# aw_801_oscilloscope.net
KiCad netlist of a schematic drawn in EAGLE
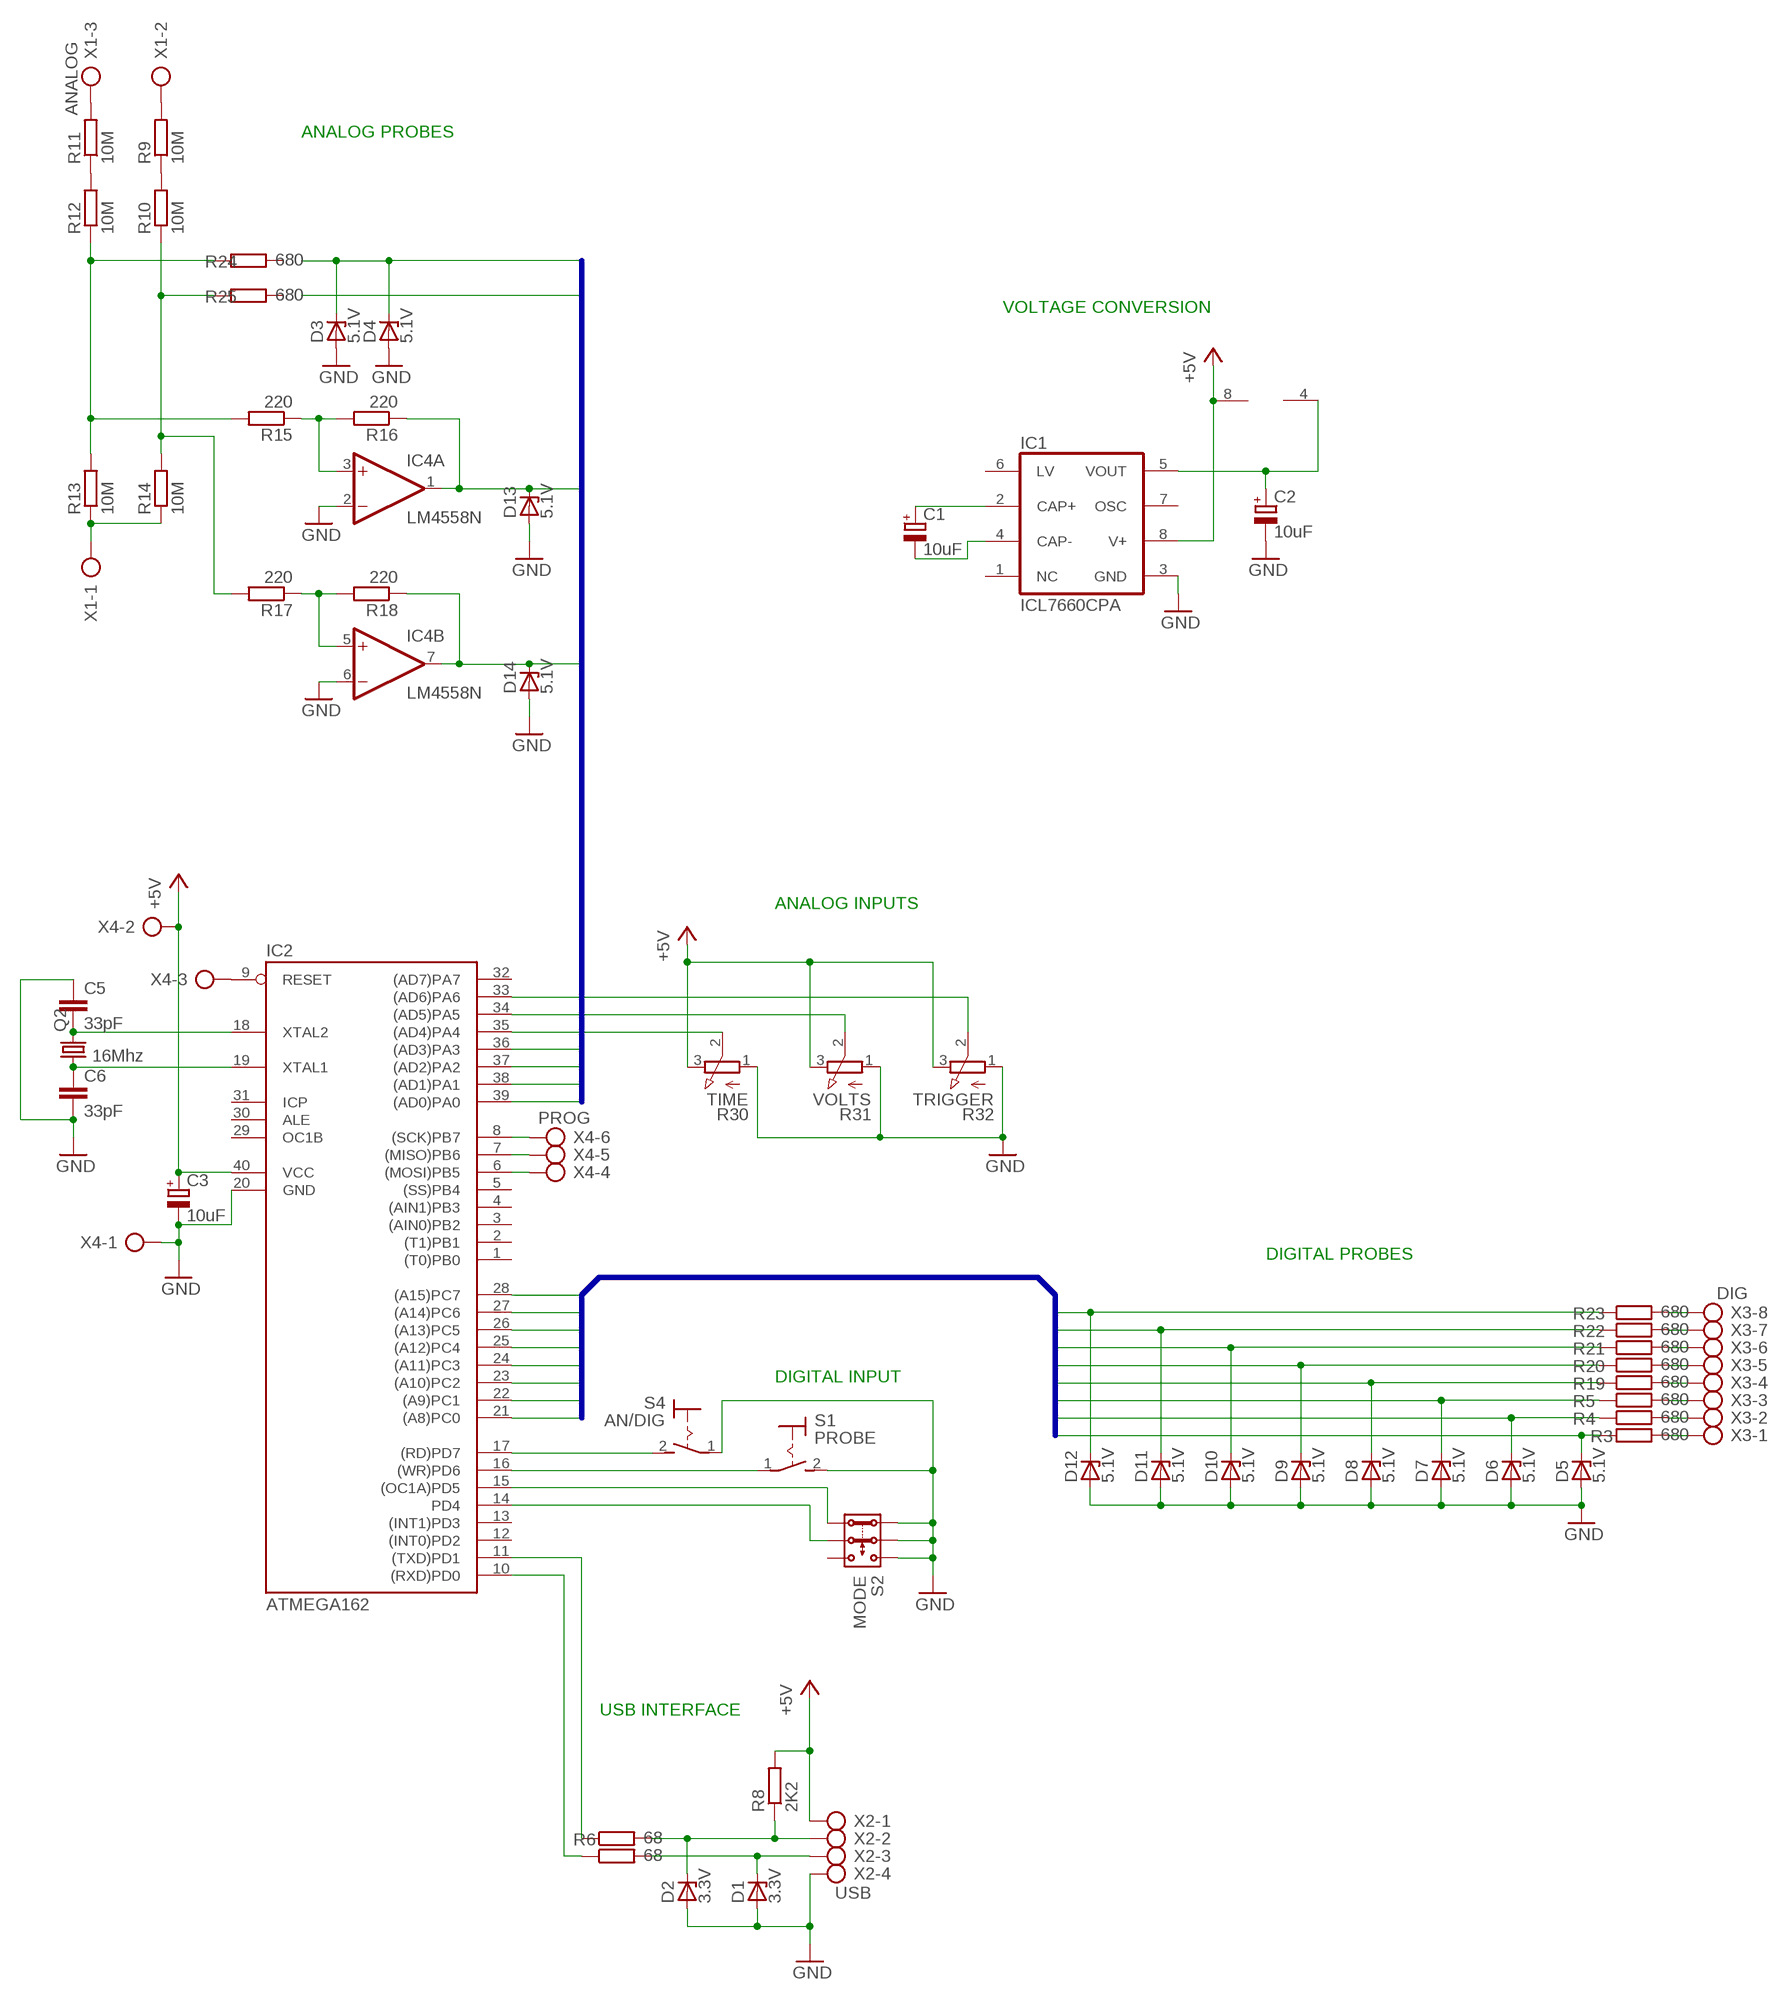
[diagram p0: schematic, sheet 1]

(export (version "E")
  (design (tool "Eeschema 10.0.6"))
  (components
    (comp (ref "C1")
      (value "10uF")
      (footprint "eagle-import:E2,5-6")
      (libsource (lib "eagle-import") (part "CPOL-EUE2.5-6"))
    )
    (comp (ref "C2")
      (value "10uF")
      (footprint "eagle-import:E2,5-6")
      (libsource (lib "eagle-import") (part "CPOL-EUE2.5-6"))
    )
    (comp (ref "C3")
      (value "10uF")
      (footprint "eagle-import:E2,5-6")
      (libsource (lib "eagle-import") (part "CPOL-EUE2.5-6"))
    )
    (comp (ref "C5")
      (value "33pF")
      (footprint "eagle-import:C050-030X075")
      (libsource (lib "eagle-import") (part "C-EU050-030X075"))
    )
    (comp (ref "C6")
      (value "33pF")
      (footprint "eagle-import:C050-030X075")
      (libsource (lib "eagle-import") (part "C-EU050-030X075"))
    )
    (comp (ref "D1")
      (value "3.3V")
      (footprint "eagle-import:DO35Z10")
      (libsource (lib "eagle-import") (part "ZENER-DIODEDO35Z10"))
    )
    (comp (ref "D2")
      (value "3.3V")
      (footprint "eagle-import:DO35Z10")
      (libsource (lib "eagle-import") (part "ZENER-DIODEDO35Z10"))
    )
    (comp (ref "D3")
      (value "5.1V")
      (footprint "eagle-import:DO35Z10")
      (libsource (lib "eagle-import") (part "ZENER-DIODEDO35Z10"))
    )
    (comp (ref "D4")
      (value "5.1V")
      (footprint "eagle-import:DO35Z10")
      (libsource (lib "eagle-import") (part "ZENER-DIODEDO35Z10"))
    )
    (comp (ref "D5")
      (value "5.1V")
      (footprint "eagle-import:DO35Z10")
      (libsource (lib "eagle-import") (part "ZENER-DIODEDO35Z10"))
    )
    (comp (ref "D6")
      (value "5.1V")
      (footprint "eagle-import:DO35Z10")
      (libsource (lib "eagle-import") (part "ZENER-DIODEDO35Z10"))
    )
    (comp (ref "D7")
      (value "5.1V")
      (footprint "eagle-import:DO35Z10")
      (libsource (lib "eagle-import") (part "ZENER-DIODEDO35Z10"))
    )
    (comp (ref "D8")
      (value "5.1V")
      (footprint "eagle-import:DO35Z10")
      (libsource (lib "eagle-import") (part "ZENER-DIODEDO35Z10"))
    )
    (comp (ref "D9")
      (value "5.1V")
      (footprint "eagle-import:DO35Z10")
      (libsource (lib "eagle-import") (part "ZENER-DIODEDO35Z10"))
    )
    (comp (ref "D10")
      (value "5.1V")
      (footprint "eagle-import:DO35Z10")
      (libsource (lib "eagle-import") (part "ZENER-DIODEDO35Z10"))
    )
    (comp (ref "D11")
      (value "5.1V")
      (footprint "eagle-import:DO35Z10")
      (libsource (lib "eagle-import") (part "ZENER-DIODEDO35Z10"))
    )
    (comp (ref "D12")
      (value "5.1V")
      (footprint "eagle-import:DO35Z10")
      (libsource (lib "eagle-import") (part "ZENER-DIODEDO35Z10"))
    )
    (comp (ref "D13")
      (value "5.1V")
      (footprint "eagle-import:DO35Z10")
      (libsource (lib "eagle-import") (part "ZENER-DIODEDO35Z10"))
    )
    (comp (ref "D14")
      (value "5.1V")
      (footprint "eagle-import:DO35Z10")
      (libsource (lib "eagle-import") (part "ZENER-DIODEDO35Z10"))
    )
    (comp (ref "IC1")
      (value "ICL7660CPA")
      (footprint "eagle-import:DIL08")
      (fields (field (name "MF") "INTERSIL"))
      (libsource (lib "eagle-import") (part "ICL7660CPA"))
    )
    (comp (ref "IC2")
      (value "ATMEGA162")
      (footprint "eagle-import:DIL40")
      (libsource (lib "eagle-import") (part "AT90S8515P"))
    )
    (comp (ref "IC4")
      (value "LM4558N")
      (footprint "eagle-import:DIL08")
      (libsource (lib "eagle-import") (part "4558NLM"))
    )
    (comp (ref "Q2")
      (value "16Mhz")
      (footprint "eagle-import:HC49U70")
      (libsource (lib "eagle-import") (part "CRYSTALHC49U70"))
    )
    (comp (ref "R3")
      (value "680")
      (footprint "eagle-import:0207_10")
      (libsource (lib "eagle-import") (part "R-EU_0207/10"))
    )
    (comp (ref "R4")
      (value "680")
      (footprint "eagle-import:0207_10")
      (libsource (lib "eagle-import") (part "R-EU_0207/10"))
    )
    (comp (ref "R5")
      (value "680")
      (footprint "eagle-import:0207_10")
      (libsource (lib "eagle-import") (part "R-EU_0207/10"))
    )
    (comp (ref "R6")
      (value "68")
      (footprint "eagle-import:0207_10")
      (libsource (lib "eagle-import") (part "R-EU_0207/10"))
    )
    (comp (ref "R7")
      (value "68")
      (footprint "eagle-import:0207_10")
      (libsource (lib "eagle-import") (part "R-EU_0207/10"))
    )
    (comp (ref "R8")
      (value "2K2")
      (footprint "eagle-import:0207_10")
      (libsource (lib "eagle-import") (part "R-EU_0207/10"))
    )
    (comp (ref "R9")
      (value "10M")
      (footprint "eagle-import:0207_10")
      (libsource (lib "eagle-import") (part "R-EU_0207/10"))
    )
    (comp (ref "R10")
      (value "10M")
      (footprint "eagle-import:0207_10")
      (libsource (lib "eagle-import") (part "R-EU_0207/10"))
    )
    (comp (ref "R11")
      (value "10M")
      (footprint "eagle-import:0207_10")
      (libsource (lib "eagle-import") (part "R-EU_0207/10"))
    )
    (comp (ref "R12")
      (value "10M")
      (footprint "eagle-import:0207_10")
      (libsource (lib "eagle-import") (part "R-EU_0207/10"))
    )
    (comp (ref "R13")
      (value "10M")
      (footprint "eagle-import:0207_10")
      (libsource (lib "eagle-import") (part "R-EU_0207/10"))
    )
    (comp (ref "R14")
      (value "10M")
      (footprint "eagle-import:0207_10")
      (libsource (lib "eagle-import") (part "R-EU_0207/10"))
    )
    (comp (ref "R15")
      (value "220")
      (footprint "eagle-import:0207_10")
      (libsource (lib "eagle-import") (part "R-EU_0207/10"))
    )
    (comp (ref "R16")
      (value "220")
      (footprint "eagle-import:0207_10")
      (libsource (lib "eagle-import") (part "R-EU_0207/10"))
    )
    (comp (ref "R17")
      (value "220")
      (footprint "eagle-import:0207_10")
      (libsource (lib "eagle-import") (part "R-EU_0207/10"))
    )
    (comp (ref "R18")
      (value "220")
      (footprint "eagle-import:0207_10")
      (libsource (lib "eagle-import") (part "R-EU_0207/10"))
    )
    (comp (ref "R19")
      (value "680")
      (footprint "eagle-import:0207_10")
      (libsource (lib "eagle-import") (part "R-EU_0207/10"))
    )
    (comp (ref "R20")
      (value "680")
      (footprint "eagle-import:0207_10")
      (libsource (lib "eagle-import") (part "R-EU_0207/10"))
    )
    (comp (ref "R21")
      (value "680")
      (footprint "eagle-import:0207_10")
      (libsource (lib "eagle-import") (part "R-EU_0207/10"))
    )
    (comp (ref "R22")
      (value "680")
      (footprint "eagle-import:0207_10")
      (libsource (lib "eagle-import") (part "R-EU_0207/10"))
    )
    (comp (ref "R23")
      (value "680")
      (footprint "eagle-import:0207_10")
      (libsource (lib "eagle-import") (part "R-EU_0207/10"))
    )
    (comp (ref "R24")
      (value "680")
      (footprint "eagle-import:0207_10")
      (libsource (lib "eagle-import") (part "R-EU_0207/10"))
    )
    (comp (ref "R25")
      (value "680")
      (footprint "eagle-import:0207_10")
      (libsource (lib "eagle-import") (part "R-EU_0207/10"))
    )
    (comp (ref "R30")
      (value "TIME")
      (footprint "eagle-import:3RP_1610N")
      (libsource (lib "eagle-import") (part "3RP/1610N"))
    )
    (comp (ref "R31")
      (value "VOLTS")
      (footprint "eagle-import:3RP_1610N")
      (libsource (lib "eagle-import") (part "3RP/1610N"))
    )
    (comp (ref "R32")
      (value "TRIGGER")
      (footprint "eagle-import:3RP_1610N")
      (libsource (lib "eagle-import") (part "3RP/1610N"))
    )
    (comp (ref "S1")
      (value "PROBE")
      (footprint "eagle-import:MS243")
      (libsource (lib "eagle-import") (part "MS243"))
    )
    (comp (ref "S2")
      (value "MODE")
      (footprint "eagle-import:2P2T")
      (libsource (lib "eagle-import") (part "2P2T"))
    )
    (comp (ref "S4")
      (value "AN/DIG")
      (footprint "eagle-import:MS243")
      (libsource (lib "eagle-import") (part "MS243"))
    )
    (comp (ref "X1")
      (value "ANALOG")
      (footprint "eagle-import:AK500_3")
      (libsource (lib "eagle-import") (part "AK500/3"))
    )
    (comp (ref "X2")
      (value "USB")
      (footprint "eagle-import:AK500_4")
      (libsource (lib "eagle-import") (part "AK500/4"))
    )
    (comp (ref "X3")
      (value "DIG")
      (footprint "eagle-import:AK500_8")
      (libsource (lib "eagle-import") (part "AK500/8"))
    )
    (comp (ref "X4")
      (value "PROG")
      (footprint "eagle-import:AK300_6")
      (libsource (lib "eagle-import") (part "AK300/6"))
    )
  )
  (nets
    (net (code "1") (name "+5V") (class "Default")
      (node (ref "C3") (pin "+") (pinfunction "+_+") (pintype "passive"))
      (node (ref "IC1") (pin "8") (pinfunction "V+_8") (pintype "power_in"))
      (node (ref "IC2") (pin "40") (pinfunction "VCC_40") (pintype "power_in"))
      (node (ref "IC4") (pin "8") (pinfunction "V+_8") (pintype "power_in"))
      (node (ref "R30") (pin "3") (pinfunction "E_3") (pintype "passive"))
      (node (ref "R31") (pin "3") (pinfunction "E_3") (pintype "passive"))
      (node (ref "R32") (pin "3") (pinfunction "E_3") (pintype "passive"))
      (node (ref "R8") (pin "2") (pinfunction "2_2") (pintype "passive"))
      (node (ref "X2") (pin "1") (pinfunction "KL_1") (pintype "passive"))
      (node (ref "X4") (pin "2") (pinfunction "KL_2") (pintype "passive"))
    )
    (net (code "2") (name "/ANALOG0") (class "Default")
      (node (ref "D3") (pin "C") (pinfunction "C_C") (pintype "passive"))
      (node (ref "D4") (pin "C") (pinfunction "C_C") (pintype "passive"))
      (node (ref "IC2") (pin "39") (pinfunction "(AD0)PA0_39") (pintype "bidirectional"))
    )
    (net (code "3") (name "/ANALOG1") (class "Default")
      (node (ref "IC2") (pin "38") (pinfunction "(AD1)PA1_38") (pintype "bidirectional"))
    )
    (net (code "4") (name "/ANALOG2") (class "Default")
      (node (ref "D13") (pin "C") (pinfunction "C_C") (pintype "passive"))
      (node (ref "IC2") (pin "37") (pinfunction "(AD2)PA2_37") (pintype "bidirectional"))
      (node (ref "IC4") (pin "1") (pinfunction "OUT_1") (pintype "output"))
      (node (ref "R16") (pin "1") (pinfunction "1_1") (pintype "passive"))
    )
    (net (code "5") (name "/ANALOG3") (class "Default")
      (node (ref "D14") (pin "C") (pinfunction "C_C") (pintype "passive"))
      (node (ref "IC2") (pin "36") (pinfunction "(AD3)PA3_36") (pintype "bidirectional"))
      (node (ref "IC4") (pin "7") (pinfunction "OUT_7") (pintype "output"))
      (node (ref "R18") (pin "1") (pinfunction "1_1") (pintype "passive"))
    )
    (net (code "6") (name "/DIG0") (class "Default")
      (node (ref "D12") (pin "C") (pinfunction "C_C") (pintype "passive"))
      (node (ref "IC2") (pin "21") (pinfunction "(A8)PC0_21") (pintype "bidirectional"))
      (node (ref "R23") (pin "1") (pinfunction "1_1") (pintype "passive"))
    )
    (net (code "7") (name "/DIG1") (class "Default")
      (node (ref "D11") (pin "C") (pinfunction "C_C") (pintype "passive"))
      (node (ref "IC2") (pin "22") (pinfunction "(A9)PC1_22") (pintype "bidirectional"))
      (node (ref "R22") (pin "1") (pinfunction "1_1") (pintype "passive"))
    )
    (net (code "8") (name "/DIG2") (class "Default")
      (node (ref "D10") (pin "C") (pinfunction "C_C") (pintype "passive"))
      (node (ref "IC2") (pin "23") (pinfunction "(A10)PC2_23") (pintype "bidirectional"))
      (node (ref "R21") (pin "1") (pinfunction "1_1") (pintype "passive"))
    )
    (net (code "9") (name "/DIG3") (class "Default")
      (node (ref "D9") (pin "C") (pinfunction "C_C") (pintype "passive"))
      (node (ref "IC2") (pin "24") (pinfunction "(A11)PC3_24") (pintype "bidirectional"))
      (node (ref "R20") (pin "1") (pinfunction "1_1") (pintype "passive"))
    )
    (net (code "10") (name "/DIG4") (class "Default")
      (node (ref "D8") (pin "C") (pinfunction "C_C") (pintype "passive"))
      (node (ref "IC2") (pin "25") (pinfunction "(A12)PC4_25") (pintype "bidirectional"))
      (node (ref "R19") (pin "1") (pinfunction "1_1") (pintype "passive"))
    )
    (net (code "11") (name "/DIG5") (class "Default")
      (node (ref "D7") (pin "C") (pinfunction "C_C") (pintype "passive"))
      (node (ref "IC2") (pin "26") (pinfunction "(A13)PC5_26") (pintype "bidirectional"))
      (node (ref "R5") (pin "1") (pinfunction "1_1") (pintype "passive"))
    )
    (net (code "12") (name "/DIG6") (class "Default")
      (node (ref "D6") (pin "C") (pinfunction "C_C") (pintype "passive"))
      (node (ref "IC2") (pin "27") (pinfunction "(A14)PC6_27") (pintype "bidirectional"))
      (node (ref "R4") (pin "1") (pinfunction "1_1") (pintype "passive"))
    )
    (net (code "13") (name "/DIG7") (class "Default")
      (node (ref "D5") (pin "C") (pinfunction "C_C") (pintype "passive"))
      (node (ref "IC2") (pin "28") (pinfunction "(A15)PC7_28") (pintype "bidirectional"))
      (node (ref "R3") (pin "1") (pinfunction "1_1") (pintype "passive"))
    )
    (net (code "14") (name "GND") (class "Default")
      (node (ref "C2") (pin "-") (pinfunction "-_-") (pintype "passive"))
      (node (ref "C3") (pin "-") (pinfunction "-_-") (pintype "passive"))
      (node (ref "C5") (pin "1") (pinfunction "1_1") (pintype "passive"))
      (node (ref "C6") (pin "2") (pinfunction "2_2") (pintype "passive"))
      (node (ref "D1") (pin "A") (pinfunction "A_A") (pintype "passive"))
      (node (ref "D10") (pin "A") (pinfunction "A_A") (pintype "passive"))
      (node (ref "D11") (pin "A") (pinfunction "A_A") (pintype "passive"))
      (node (ref "D12") (pin "A") (pinfunction "A_A") (pintype "passive"))
      (node (ref "D13") (pin "A") (pinfunction "A_A") (pintype "passive"))
      (node (ref "D14") (pin "A") (pinfunction "A_A") (pintype "passive"))
      (node (ref "D2") (pin "A") (pinfunction "A_A") (pintype "passive"))
      (node (ref "D3") (pin "A") (pinfunction "A_A") (pintype "passive"))
      (node (ref "D4") (pin "A") (pinfunction "A_A") (pintype "passive"))
      (node (ref "D5") (pin "A") (pinfunction "A_A") (pintype "passive"))
      (node (ref "D6") (pin "A") (pinfunction "A_A") (pintype "passive"))
      (node (ref "D7") (pin "A") (pinfunction "A_A") (pintype "passive"))
      (node (ref "D8") (pin "A") (pinfunction "A_A") (pintype "passive"))
      (node (ref "D9") (pin "A") (pinfunction "A_A") (pintype "passive"))
      (node (ref "IC1") (pin "3") (pinfunction "GND_3") (pintype "power_in"))
      (node (ref "IC2") (pin "20") (pinfunction "GND_20") (pintype "power_in"))
      (node (ref "IC4") (pin "2") (pinfunction "-IN_2") (pintype "input"))
      (node (ref "IC4") (pin "6") (pinfunction "-IN_6") (pintype "input"))
      (node (ref "R30") (pin "1") (pinfunction "A_1") (pintype "passive"))
      (node (ref "R31") (pin "1") (pinfunction "A_1") (pintype "passive"))
      (node (ref "R32") (pin "1") (pinfunction "A_1") (pintype "passive"))
      (node (ref "S1") (pin "2") (pinfunction "S_2") (pintype "passive"))
      (node (ref "S2") (pin "1.1") (pinfunction "1.1_1.1") (pintype "passive"))
      (node (ref "S2") (pin "2.1") (pinfunction "2.1_2.1") (pintype "passive"))
      (node (ref "S2") (pin "3.1") (pinfunction "3.1_3.1") (pintype "passive"))
      (node (ref "S4") (pin "1") (pinfunction "P_1") (pintype "passive"))
      (node (ref "X2") (pin "4") (pinfunction "KL_4") (pintype "passive"))
      (node (ref "X4") (pin "1") (pinfunction "KL_1") (pintype "passive"))
    )
    (net (code "15") (name "Net-(IC1-CAP+)") (class "Default")
      (node (ref "C1") (pin "+") (pinfunction "+_+") (pintype "passive"))
      (node (ref "IC1") (pin "2") (pinfunction "CAP+_2") (pintype "passive"))
    )
    (net (code "16") (name "Net-(IC1-CAP-)") (class "Default")
      (node (ref "C1") (pin "-") (pinfunction "-_-") (pintype "passive"))
      (node (ref "IC1") (pin "4") (pinfunction "CAP-_4") (pintype "passive"))
    )
    (net (code "17") (name "Net-(IC1-VOUT)") (class "Default")
      (node (ref "C2") (pin "+") (pinfunction "+_+") (pintype "passive"))
      (node (ref "IC1") (pin "5") (pinfunction "VOUT_5") (pintype "power_in"))
      (node (ref "IC4") (pin "4") (pinfunction "V-_4") (pintype "power_in"))
    )
    (net (code "18") (name "Net-(IC2-(AD4)PA4)") (class "Default")
      (node (ref "IC2") (pin "35") (pinfunction "(AD4)PA4_35") (pintype "bidirectional"))
      (node (ref "R30") (pin "2") (pinfunction "S_2") (pintype "passive"))
    )
    (net (code "19") (name "Net-(IC2-(AD5)PA5)") (class "Default")
      (node (ref "IC2") (pin "34") (pinfunction "(AD5)PA5_34") (pintype "bidirectional"))
      (node (ref "R31") (pin "2") (pinfunction "S_2") (pintype "passive"))
    )
    (net (code "20") (name "Net-(IC2-(AD6)PA6)") (class "Default")
      (node (ref "IC2") (pin "33") (pinfunction "(AD6)PA6_33") (pintype "bidirectional"))
      (node (ref "R32") (pin "2") (pinfunction "S_2") (pintype "passive"))
    )
    (net (code "21") (name "Net-(IC2-(MISO)PB6)") (class "Default")
      (node (ref "IC2") (pin "7") (pinfunction "(MISO)PB6_7") (pintype "bidirectional"))
      (node (ref "X4") (pin "5") (pinfunction "KL_5") (pintype "passive"))
    )
    (net (code "22") (name "Net-(IC2-(MOSI)PB5)") (class "Default")
      (node (ref "IC2") (pin "6") (pinfunction "(MOSI)PB5_6") (pintype "bidirectional"))
      (node (ref "X4") (pin "4") (pinfunction "KL_4") (pintype "passive"))
    )
    (net (code "23") (name "Net-(IC2-(OC1A)PD5)") (class "Default")
      (node (ref "IC2") (pin "15") (pinfunction "(OC1A)PD5_15") (pintype "bidirectional"))
      (node (ref "S2") (pin "1.2") (pinfunction "1.2_1.2") (pintype "passive"))
    )
    (net (code "24") (name "Net-(IC2-(RD)PD7)") (class "Default")
      (node (ref "IC2") (pin "17") (pinfunction "(RD)PD7_17") (pintype "bidirectional"))
      (node (ref "S4") (pin "2") (pinfunction "S_2") (pintype "passive"))
    )
    (net (code "25") (name "Net-(IC2-(RXD)PD0)") (class "Default")
      (node (ref "IC2") (pin "10") (pinfunction "(RXD)PD0_10") (pintype "bidirectional"))
      (node (ref "R7") (pin "1") (pinfunction "1_1") (pintype "passive"))
    )
    (net (code "26") (name "Net-(IC2-(SCK)PB7)") (class "Default")
      (node (ref "IC2") (pin "8") (pinfunction "(SCK)PB7_8") (pintype "bidirectional"))
      (node (ref "X4") (pin "6") (pinfunction "KL_6") (pintype "passive"))
    )
    (net (code "27") (name "Net-(IC2-(TXD)PD1)") (class "Default")
      (node (ref "IC2") (pin "11") (pinfunction "(TXD)PD1_11") (pintype "bidirectional"))
      (node (ref "R6") (pin "1") (pinfunction "1_1") (pintype "passive"))
    )
    (net (code "28") (name "Net-(IC2-(WR)PD6)") (class "Default")
      (node (ref "IC2") (pin "16") (pinfunction "(WR)PD6_16") (pintype "bidirectional"))
      (node (ref "S1") (pin "1") (pinfunction "P_1") (pintype "passive"))
    )
    (net (code "29") (name "Net-(IC2-PD4)") (class "Default")
      (node (ref "IC2") (pin "14") (pinfunction "PD4_14") (pintype "bidirectional"))
      (node (ref "S2") (pin "2.2") (pinfunction "2.2_2.2") (pintype "passive"))
    )
    (net (code "30") (name "Net-(IC2-RESET)") (class "Default")
      (node (ref "IC2") (pin "9") (pinfunction "RESET_9") (pintype "input"))
      (node (ref "X4") (pin "3") (pinfunction "KL_3") (pintype "passive"))
    )
    (net (code "31") (name "Net-(IC2-XTAL1)") (class "Default")
      (node (ref "C6") (pin "1") (pinfunction "1_1") (pintype "passive"))
      (node (ref "IC2") (pin "19") (pinfunction "XTAL1_19") (pintype "bidirectional"))
      (node (ref "Q2") (pin "1") (pinfunction "1_1") (pintype "passive"))
    )
    (net (code "32") (name "Net-(IC2-XTAL2)") (class "Default")
      (node (ref "C5") (pin "2") (pinfunction "2_2") (pintype "passive"))
      (node (ref "IC2") (pin "18") (pinfunction "XTAL2_18") (pintype "bidirectional"))
      (node (ref "Q2") (pin "2") (pinfunction "2_2") (pintype "passive"))
    )
    (net (code "33") (name "Net-(IC4A-+IN)") (class "Default")
      (node (ref "IC4") (pin "3") (pinfunction "+IN_3") (pintype "input"))
      (node (ref "R15") (pin "1") (pinfunction "1_1") (pintype "passive"))
      (node (ref "R16") (pin "2") (pinfunction "2_2") (pintype "passive"))
    )
    (net (code "34") (name "Net-(IC4B-+IN)") (class "Default")
      (node (ref "IC4") (pin "5") (pinfunction "+IN_5") (pintype "input"))
      (node (ref "R17") (pin "1") (pinfunction "1_1") (pintype "passive"))
      (node (ref "R18") (pin "2") (pinfunction "2_2") (pintype "passive"))
    )
    (net (code "35") (name "Net-(R10-Pad1)") (class "Default")
      (node (ref "R10") (pin "1") (pinfunction "1_1") (pintype "passive"))
      (node (ref "R14") (pin "2") (pinfunction "2_2") (pintype "passive"))
      (node (ref "R17") (pin "2") (pinfunction "2_2") (pintype "passive"))
      (node (ref "R25") (pin "1") (pinfunction "1_1") (pintype "passive"))
    )
    (net (code "36") (name "Net-(R10-Pad2)") (class "Default")
      (node (ref "R10") (pin "2") (pinfunction "2_2") (pintype "passive"))
      (node (ref "R9") (pin "1") (pinfunction "1_1") (pintype "passive"))
    )
    (net (code "37") (name "Net-(R11-Pad1)") (class "Default")
      (node (ref "R11") (pin "1") (pinfunction "1_1") (pintype "passive"))
      (node (ref "R12") (pin "2") (pinfunction "2_2") (pintype "passive"))
    )
    (net (code "38") (name "Net-(R12-Pad1)") (class "Default")
      (node (ref "R12") (pin "1") (pinfunction "1_1") (pintype "passive"))
      (node (ref "R13") (pin "2") (pinfunction "2_2") (pintype "passive"))
      (node (ref "R15") (pin "2") (pinfunction "2_2") (pintype "passive"))
      (node (ref "R24") (pin "1") (pinfunction "1_1") (pintype "passive"))
    )
    (net (code "39") (name "Net-(X1A-KL)") (class "Default")
      (node (ref "R13") (pin "1") (pinfunction "1_1") (pintype "passive"))
      (node (ref "R14") (pin "1") (pinfunction "1_1") (pintype "passive"))
      (node (ref "X1") (pin "1") (pinfunction "KL_1") (pintype "passive"))
    )
    (net (code "40") (name "Net-(X1B-KL)") (class "Default")
      (node (ref "R9") (pin "2") (pinfunction "2_2") (pintype "passive"))
      (node (ref "X1") (pin "2") (pinfunction "KL_2") (pintype "passive"))
    )
    (net (code "41") (name "Net-(X1C-KL)") (class "Default")
      (node (ref "R11") (pin "2") (pinfunction "2_2") (pintype "passive"))
      (node (ref "X1") (pin "3") (pinfunction "KL_3") (pintype "passive"))
    )
    (net (code "42") (name "Net-(X2B-KL)") (class "Default")
      (node (ref "D2") (pin "C") (pinfunction "C_C") (pintype "passive"))
      (node (ref "R6") (pin "2") (pinfunction "2_2") (pintype "passive"))
      (node (ref "R8") (pin "1") (pinfunction "1_1") (pintype "passive"))
      (node (ref "X2") (pin "2") (pinfunction "KL_2") (pintype "passive"))
    )
    (net (code "43") (name "Net-(X2C-KL)") (class "Default")
      (node (ref "D1") (pin "C") (pinfunction "C_C") (pintype "passive"))
      (node (ref "R7") (pin "2") (pinfunction "2_2") (pintype "passive"))
      (node (ref "X2") (pin "3") (pinfunction "KL_3") (pintype "passive"))
    )
    (net (code "44") (name "Net-(X3A-KL)") (class "Default")
      (node (ref "R3") (pin "2") (pinfunction "2_2") (pintype "passive"))
      (node (ref "X3") (pin "1") (pinfunction "KL_1") (pintype "passive"))
    )
    (net (code "45") (name "Net-(X3B-KL)") (class "Default")
      (node (ref "R4") (pin "2") (pinfunction "2_2") (pintype "passive"))
      (node (ref "X3") (pin "2") (pinfunction "KL_2") (pintype "passive"))
    )
    (net (code "46") (name "Net-(X3C-KL)") (class "Default")
      (node (ref "R5") (pin "2") (pinfunction "2_2") (pintype "passive"))
      (node (ref "X3") (pin "3") (pinfunction "KL_3") (pintype "passive"))
    )
    (net (code "47") (name "Net-(X3D-KL)") (class "Default")
      (node (ref "R19") (pin "2") (pinfunction "2_2") (pintype "passive"))
      (node (ref "X3") (pin "4") (pinfunction "KL_4") (pintype "passive"))
    )
    (net (code "48") (name "Net-(X3E-KL)") (class "Default")
      (node (ref "R20") (pin "2") (pinfunction "2_2") (pintype "passive"))
      (node (ref "X3") (pin "5") (pinfunction "KL_5") (pintype "passive"))
    )
    (net (code "49") (name "Net-(X3F-KL)") (class "Default")
      (node (ref "R21") (pin "2") (pinfunction "2_2") (pintype "passive"))
      (node (ref "X3") (pin "6") (pinfunction "KL_6") (pintype "passive"))
    )
    (net (code "50") (name "Net-(X3G-KL)") (class "Default")
      (node (ref "R22") (pin "2") (pinfunction "2_2") (pintype "passive"))
      (node (ref "X3") (pin "7") (pinfunction "KL_7") (pintype "passive"))
    )
    (net (code "51") (name "Net-(X3H-KL)") (class "Default")
      (node (ref "R23") (pin "2") (pinfunction "2_2") (pintype "passive"))
      (node (ref "X3") (pin "8") (pinfunction "KL_8") (pintype "passive"))
    )
    (net (code "52") (name "unconnected-(IC1-LV-Pad6)") (class "Default")
      (node (ref "IC1") (pin "6") (pinfunction "LV_6") (pintype "passive"))
    )
    (net (code "53") (name "unconnected-(IC1-NC-Pad1)") (class "Default")
      (node (ref "IC1") (pin "1") (pinfunction "NC_1") (pintype "no_connect"))
    )
    (net (code "54") (name "unconnected-(IC1-OSC-Pad7)") (class "Default")
      (node (ref "IC1") (pin "7") (pinfunction "OSC_7") (pintype "output"))
    )
    (net (code "55") (name "unconnected-(IC2-(AD7)PA7-Pad32)") (class "Default")
      (node (ref "IC2") (pin "32") (pinfunction "(AD7)PA7_32") (pintype "bidirectional"))
    )
    (net (code "56") (name "unconnected-(IC2-(AIN0)PB2-Pad3)") (class "Default")
      (node (ref "IC2") (pin "3") (pinfunction "(AIN0)PB2_3") (pintype "bidirectional"))
    )
    (net (code "57") (name "unconnected-(IC2-(AIN1)PB3-Pad4)") (class "Default")
      (node (ref "IC2") (pin "4") (pinfunction "(AIN1)PB3_4") (pintype "bidirectional"))
    )
    (net (code "58") (name "unconnected-(IC2-(INT0)PD2-Pad12)") (class "Default")
      (node (ref "IC2") (pin "12") (pinfunction "(INT0)PD2_12") (pintype "bidirectional"))
    )
    (net (code "59") (name "unconnected-(IC2-(INT1)PD3-Pad13)") (class "Default")
      (node (ref "IC2") (pin "13") (pinfunction "(INT1)PD3_13") (pintype "bidirectional"))
    )
    (net (code "60") (name "unconnected-(IC2-(SS)PB4-Pad5)") (class "Default")
      (node (ref "IC2") (pin "5") (pinfunction "(SS)PB4_5") (pintype "bidirectional"))
    )
    (net (code "61") (name "unconnected-(IC2-(T0)PB0-Pad1)") (class "Default")
      (node (ref "IC2") (pin "1") (pinfunction "(T0)PB0_1") (pintype "bidirectional"))
    )
    (net (code "62") (name "unconnected-(IC2-(T1)PB1-Pad2)") (class "Default")
      (node (ref "IC2") (pin "2") (pinfunction "(T1)PB1_2") (pintype "bidirectional"))
    )
    (net (code "63") (name "unconnected-(IC2-ALE-Pad30)") (class "Default")
      (node (ref "IC2") (pin "30") (pinfunction "ALE_30") (pintype "bidirectional"))
    )
    (net (code "64") (name "unconnected-(IC2-ICP-Pad31)") (class "Default")
      (node (ref "IC2") (pin "31") (pinfunction "ICP_31") (pintype "bidirectional"))
    )
    (net (code "65") (name "unconnected-(IC2-OC1B-Pad29)") (class "Default")
      (node (ref "IC2") (pin "29") (pinfunction "OC1B_29") (pintype "bidirectional"))
    )
    (net (code "66") (name "unconnected-(R24-Pad2)") (class "Default")
      (node (ref "R24") (pin "2") (pinfunction "2_2") (pintype "passive"))
    )
    (net (code "67") (name "unconnected-(R25-Pad2)") (class "Default")
      (node (ref "R25") (pin "2") (pinfunction "2_2") (pintype "passive"))
    )
    (net (code "68") (name "unconnected-(S2-Pad3.2)") (class "Default")
      (node (ref "S2") (pin "3.2") (pinfunction "3.2_3.2") (pintype "passive"))
    )
  )
)
